# Camera.net
KiCad netlist of a schematic drawn in Altium Designer
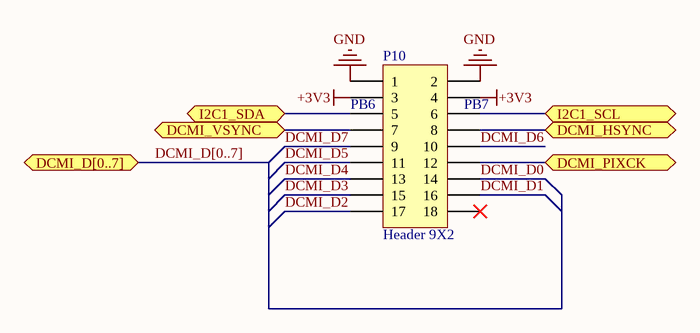
[diagram p0: Camera.SchDoc]

(export (version "E")
  (design (tool "Eeschema 10.0.6"))
  (components
    (comp (ref "P10")
      (value "Header 9X2")
      (footprint "HDR2X9")
      (description "Header, 9-Pin, Dual row")
      (fields (field (name "PUBLISHER") "Altium Limited"))
      (libsource (lib "Miscellaneous Connectors") (part "Header 9X2"))
    )
  )
  (nets
    (net (code "1") (name "+3V3") (class "Default")
      (node (ref "P10") (pin "3") (pinfunction "3_3") (pintype "passive"))
      (node (ref "P10") (pin "4") (pinfunction "4_4") (pintype "passive"))
    )
    (net (code "2") (name "/DCMI_D0") (class "Default")
      (node (ref "P10") (pin "14") (pinfunction "14_14") (pintype "passive"))
    )
    (net (code "3") (name "/DCMI_D1") (class "Default")
      (node (ref "P10") (pin "16") (pinfunction "16_16") (pintype "passive"))
    )
    (net (code "4") (name "/DCMI_D2") (class "Default")
      (node (ref "P10") (pin "17") (pinfunction "17_17") (pintype "passive"))
    )
    (net (code "5") (name "/DCMI_D3") (class "Default")
      (node (ref "P10") (pin "15") (pinfunction "15_15") (pintype "passive"))
    )
    (net (code "6") (name "/DCMI_D4") (class "Default")
      (node (ref "P10") (pin "13") (pinfunction "13_13") (pintype "passive"))
    )
    (net (code "7") (name "/DCMI_D5") (class "Default")
      (node (ref "P10") (pin "11") (pinfunction "11_11") (pintype "passive"))
    )
    (net (code "8") (name "/DCMI_D6") (class "Default")
      (node (ref "P10") (pin "10") (pinfunction "10_10") (pintype "passive"))
    )
    (net (code "9") (name "/DCMI_D7") (class "Default")
      (node (ref "P10") (pin "9") (pinfunction "9_9") (pintype "passive"))
    )
    (net (code "11") (name "/DCMI_HSYNC") (class "Default")
      (node (ref "P10") (pin "8") (pinfunction "8_8") (pintype "passive"))
    )
    (net (code "12") (name "/DCMI_PIXCK") (class "Default")
      (node (ref "P10") (pin "12") (pinfunction "12_12") (pintype "passive"))
    )
    (net (code "13") (name "/DCMI_VSYNC") (class "Default")
      (node (ref "P10") (pin "7") (pinfunction "7_7") (pintype "passive"))
    )
    (net (code "14") (name "/I2C1_SCL") (class "Default")
      (node (ref "P10") (pin "6") (pinfunction "6_6") (pintype "passive"))
    )
    (net (code "15") (name "/I2C1_SDA") (class "Default")
      (node (ref "P10") (pin "5") (pinfunction "5_5") (pintype "passive"))
    )
    (net (code "16") (name "GND") (class "Default")
      (node (ref "P10") (pin "1") (pinfunction "1_1") (pintype "passive"))
      (node (ref "P10") (pin "2") (pinfunction "2_2") (pintype "passive"))
    )
    (net (code "17") (name "unconnected-(P10-Pad18)") (class "Default")
      (node (ref "P10") (pin "18") (pinfunction "18_18") (pintype "passive+no_connect"))
    )
  )
)
